# R7FA2E1A7_LED.net
KiCad netlist of a schematic drawn in EasyEDA Pro
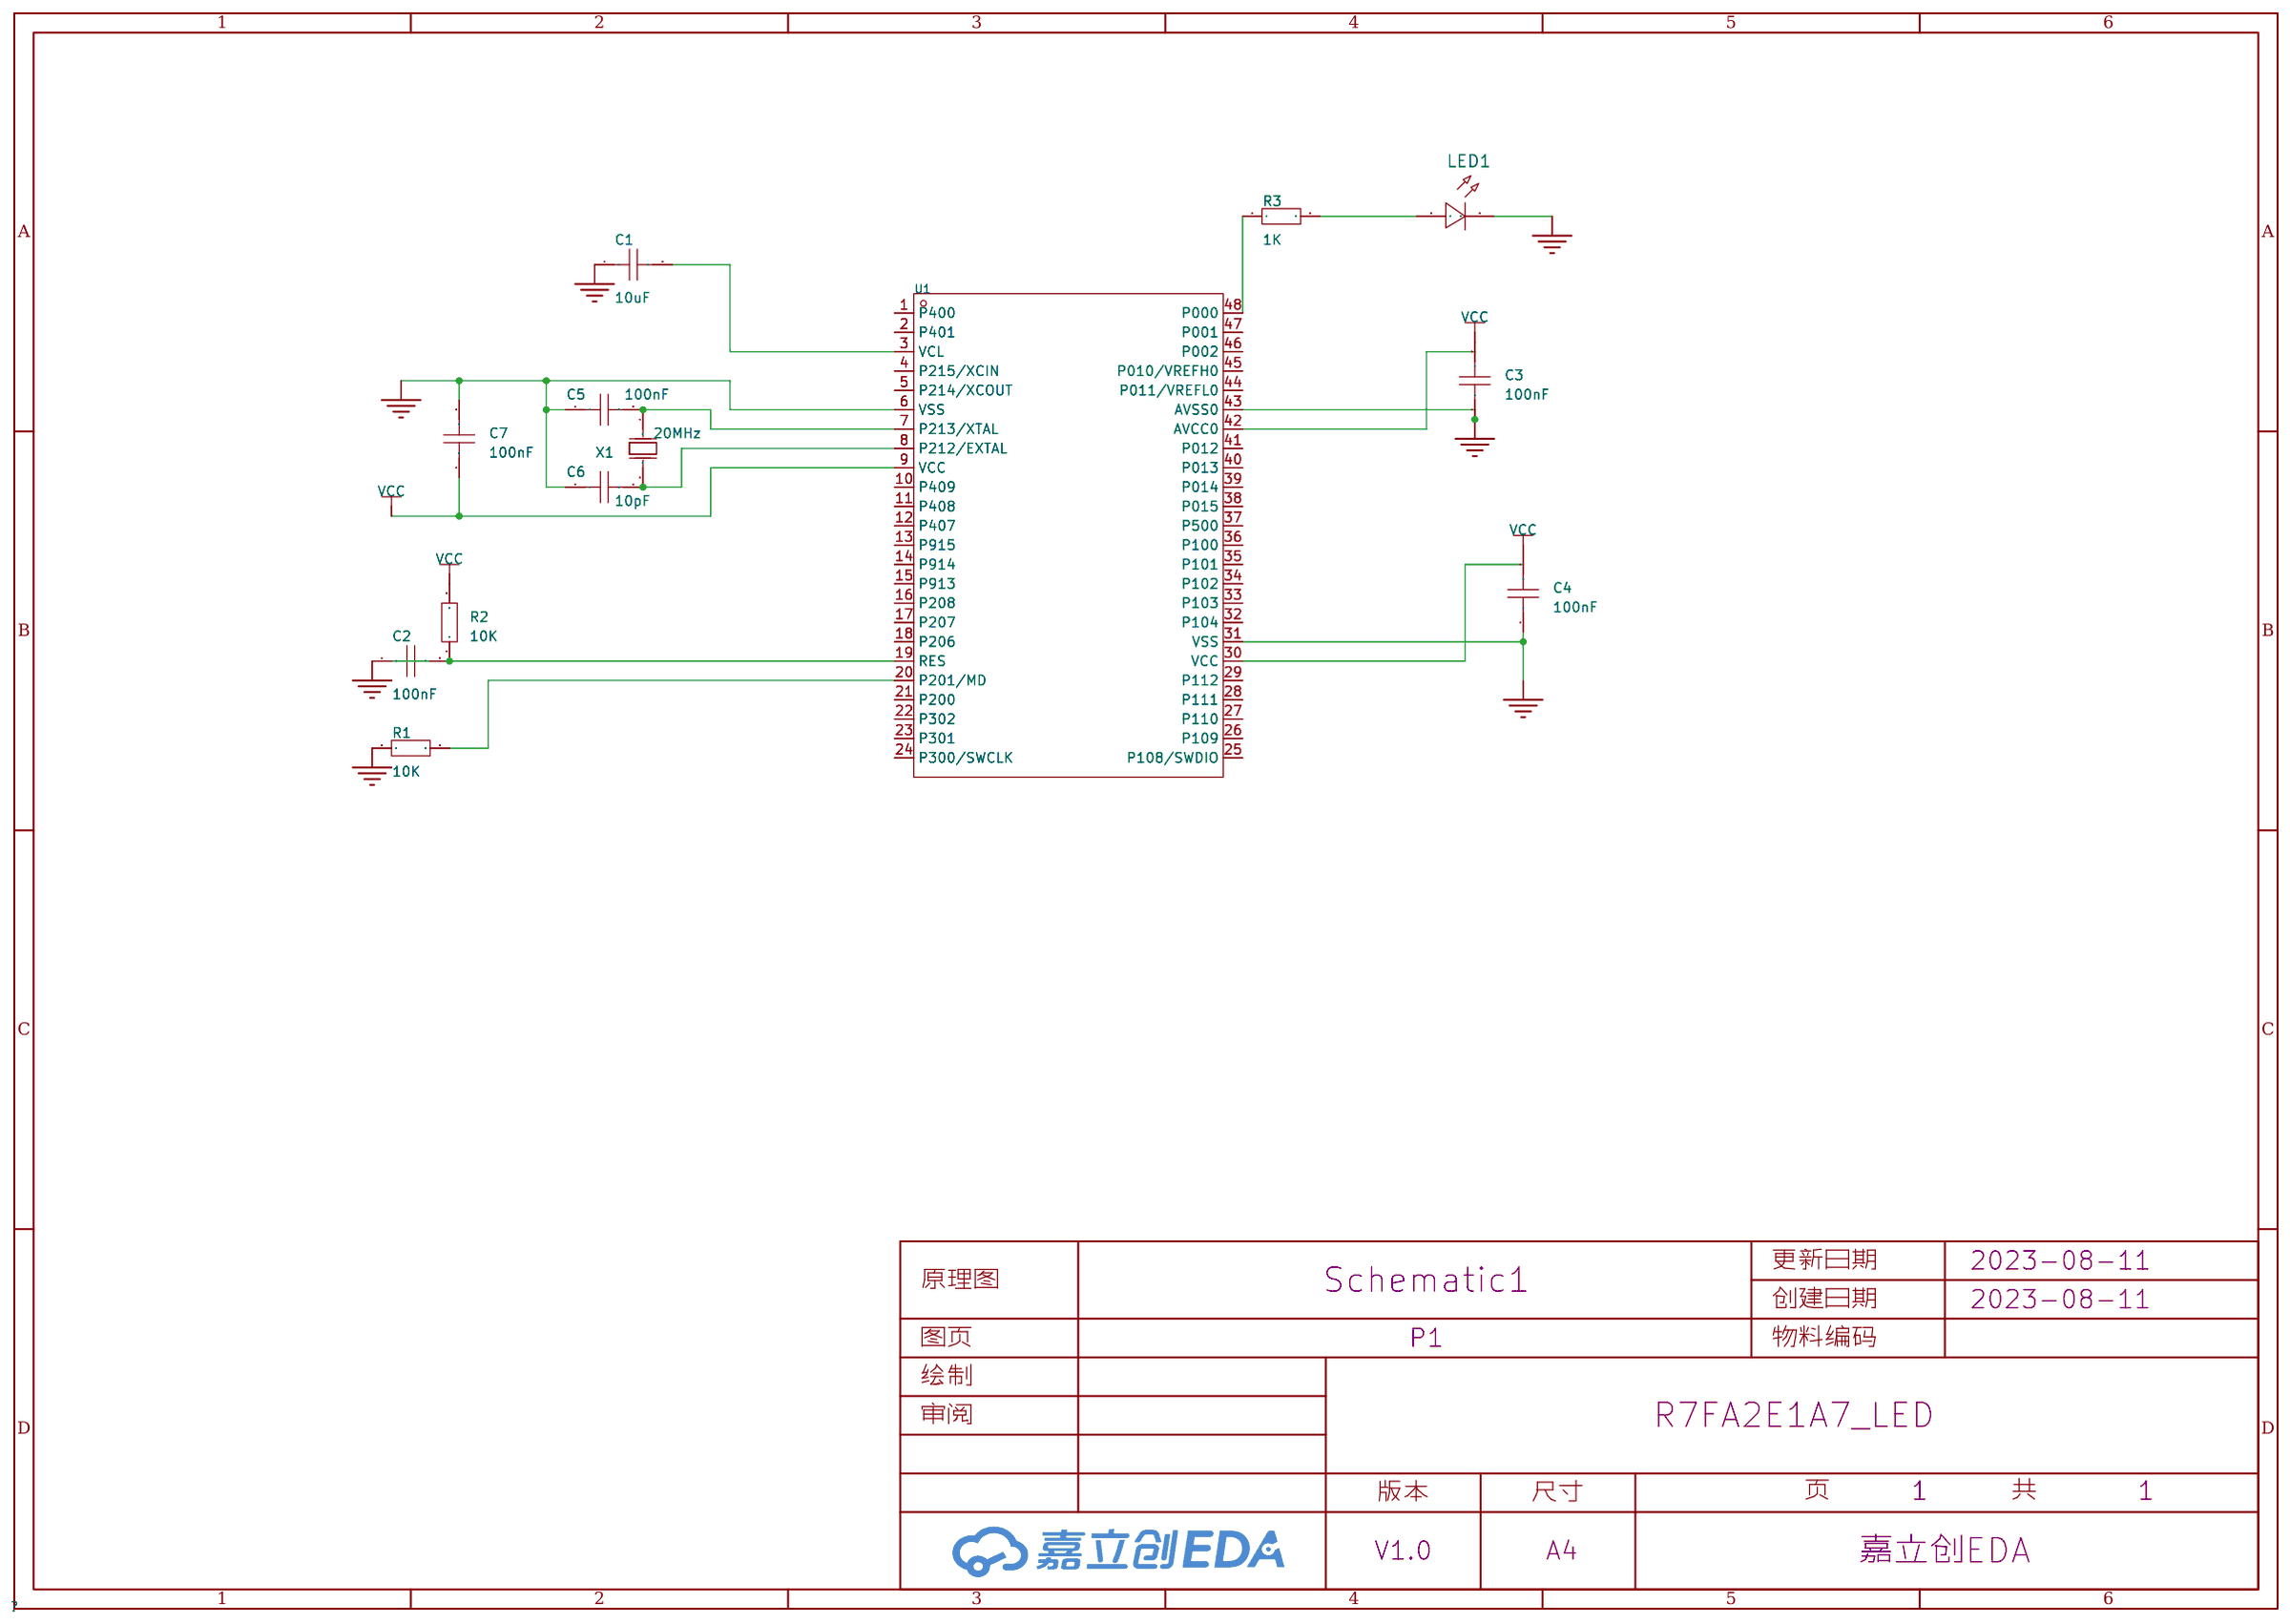
[diagram p0: schematic sheet]

(export (version "E")
  (design (tool "Eeschema 10.0.6"))
  (components
    (comp (ref "C1")
      (value "10uF")
      (footprint "easyedapro:C0603")
      (libsource (lib "easyedapro") (part "CapAcitance"))
    )
    (comp (ref "C2")
      (value "100nF")
      (footprint "easyedapro:C0603")
      (libsource (lib "easyedapro") (part "CapAcitance"))
    )
    (comp (ref "C3")
      (value "100nF")
      (footprint "easyedapro:C0603")
      (libsource (lib "easyedapro") (part "CapAcitance"))
    )
    (comp (ref "C4")
      (value "100nF")
      (footprint "easyedapro:C0603")
      (libsource (lib "easyedapro") (part "CapAcitance"))
    )
    (comp (ref "C5")
      (value "100nF")
      (footprint "easyedapro:C0603")
      (libsource (lib "easyedapro") (part "CapAcitance"))
    )
    (comp (ref "C6")
      (value "10pF")
      (footprint "easyedapro:C0603")
      (libsource (lib "easyedapro") (part "CapAcitance"))
    )
    (comp (ref "C7")
      (value "100nF")
      (footprint "easyedapro:C0603")
      (libsource (lib "easyedapro") (part "CapAcitance"))
    )
    (comp (ref "LED1")
      (value "~")
      (footprint "easyedapro:LED_0603")
      (libsource (lib "easyedapro") (part "LED_R"))
    )
    (comp (ref "R1") (value "10K") (footprint "easyedapro:R0603") (libsource (lib "easyedapro") (part "电阻")))
    (comp (ref "R2") (value "10K") (footprint "easyedapro:R0603") (libsource (lib "easyedapro") (part "电阻")))
    (comp (ref "R3") (value "1K") (footprint "easyedapro:R0603") (libsource (lib "easyedapro") (part "电阻")))
    (comp (ref "U1")
      (value "R7FA2E1A72DFL#AA0")
      (footprint "easyedapro:LQFP-48_L7.0-W7.0-P0.50-LS9.0-BL")
      (description "CPU内核:ARM Cortex-M23;CPU最大主频:48MHz;工作电压范围:1.6V~5.5V;程序存储容量:64KB;RAM总容量:16KB;GPIO端口数量:40;")
      (fields (field (name "Manufacturer") "RENESAS(瑞萨)/IDT"))
      (libsource (lib "easyedapro") (part "R7FA2E1A72DFL#AA0"))
    )
    (comp (ref "X1")
      (value "20MHz")
      (footprint "easyedapro:OSC-TH_L10.0-W4.5-P5.00")
      (description "频率:20MHz;频率公差:±10ppm;负载电容:15pF;")
      (fields (field (name "Manufacturer Part") "X49SD20MPB2SC") (field (name "Manufacturer") "YXC(扬兴晶振)"))
      (libsource (lib "easyedapro") (part "X49SD20MPB2SC"))
    )
  )
  (nets
    (net (code "1") (name "GND") (class "Default")
      (node (ref "C1") (pin "1") (pinfunction "1_1") (pintype "input"))
      (node (ref "C2") (pin "1") (pinfunction "1_1") (pintype "input"))
      (node (ref "C3") (pin "1") (pinfunction "1_1") (pintype "input"))
      (node (ref "C4") (pin "1") (pinfunction "1_1") (pintype "input"))
      (node (ref "C5") (pin "1") (pinfunction "1_1") (pintype "input"))
      (node (ref "C6") (pin "1") (pinfunction "1_1") (pintype "input"))
      (node (ref "C7") (pin "2") (pinfunction "2_2") (pintype "input"))
      (node (ref "LED1") (pin "1") (pinfunction "C_1") (pintype "input"))
      (node (ref "R1") (pin "1") (pinfunction "1_1") (pintype "input"))
      (node (ref "U1") (pin "31") (pinfunction "VSS_31") (pintype "input"))
      (node (ref "U1") (pin "43") (pinfunction "AVSS0_43") (pintype "input"))
      (node (ref "U1") (pin "6") (pinfunction "VSS_6") (pintype "input"))
    )
    (net (code "2") (name "Net-(LED1-A)") (class "Default")
      (node (ref "LED1") (pin "2") (pinfunction "A_2") (pintype "input"))
      (node (ref "R3") (pin "2") (pinfunction "2_2") (pintype "input"))
    )
    (net (code "3") (name "Net-(U1-P000)") (class "Default")
      (node (ref "R3") (pin "1") (pinfunction "1_1") (pintype "input"))
      (node (ref "U1") (pin "48") (pinfunction "P000_48") (pintype "input"))
    )
    (net (code "4") (name "Net-(U1-P201{slash}MD)") (class "Default")
      (node (ref "R1") (pin "2") (pinfunction "2_2") (pintype "input"))
      (node (ref "U1") (pin "20") (pinfunction "P201/MD_20") (pintype "input"))
    )
    (net (code "5") (name "Net-(U1-P212{slash}EXTAL)") (class "Default")
      (node (ref "C6") (pin "2") (pinfunction "2_2") (pintype "input"))
      (node (ref "U1") (pin "8") (pinfunction "P212/EXTAL_8") (pintype "input"))
      (node (ref "X1") (pin "2") (pinfunction "OSC2_2") (pintype "input"))
    )
    (net (code "6") (name "Net-(U1-P213{slash}XTAL)") (class "Default")
      (node (ref "C5") (pin "2") (pinfunction "2_2") (pintype "input"))
      (node (ref "U1") (pin "7") (pinfunction "P213/XTAL_7") (pintype "input"))
      (node (ref "X1") (pin "1") (pinfunction "OSC1_1") (pintype "input"))
    )
    (net (code "7") (name "Net-(U1-RES)") (class "Default")
      (node (ref "C2") (pin "2") (pinfunction "2_2") (pintype "input"))
      (node (ref "R2") (pin "1") (pinfunction "1_1") (pintype "input"))
      (node (ref "U1") (pin "19") (pinfunction "RES_19") (pintype "input"))
    )
    (net (code "8") (name "Net-(U1-VCL)") (class "Default")
      (node (ref "C1") (pin "2") (pinfunction "2_2") (pintype "input"))
      (node (ref "U1") (pin "3") (pinfunction "VCL_3") (pintype "input"))
    )
    (net (code "9") (name "VCC") (class "Default")
      (node (ref "C3") (pin "2") (pinfunction "2_2") (pintype "input"))
      (node (ref "C4") (pin "2") (pinfunction "2_2") (pintype "input"))
      (node (ref "C7") (pin "1") (pinfunction "1_1") (pintype "input"))
      (node (ref "R2") (pin "2") (pinfunction "2_2") (pintype "input"))
      (node (ref "U1") (pin "9") (pinfunction "VCC_9") (pintype "input"))
    )
    (net (code "10") (name "unconnected-(U1-AVCC0-Pad42)") (class "Default")
      (node (ref "U1") (pin "42") (pinfunction "AVCC0_42") (pintype "input"))
    )
    (net (code "11") (name "unconnected-(U1-P001-Pad47)") (class "Default")
      (node (ref "U1") (pin "47") (pinfunction "P001_47") (pintype "input"))
    )
    (net (code "12") (name "unconnected-(U1-P002-Pad46)") (class "Default")
      (node (ref "U1") (pin "46") (pinfunction "P002_46") (pintype "input"))
    )
    (net (code "13") (name "unconnected-(U1-P010{slash}VREFH0-Pad45)") (class "Default")
      (node (ref "U1") (pin "45") (pinfunction "P010/VREFH0_45") (pintype "input"))
    )
    (net (code "14") (name "unconnected-(U1-P011{slash}VREFL0-Pad44)") (class "Default")
      (node (ref "U1") (pin "44") (pinfunction "P011/VREFL0_44") (pintype "input"))
    )
    (net (code "15") (name "unconnected-(U1-P012-Pad41)") (class "Default")
      (node (ref "U1") (pin "41") (pinfunction "P012_41") (pintype "input"))
    )
    (net (code "16") (name "unconnected-(U1-P013-Pad40)") (class "Default")
      (node (ref "U1") (pin "40") (pinfunction "P013_40") (pintype "input"))
    )
    (net (code "17") (name "unconnected-(U1-P014-Pad39)") (class "Default")
      (node (ref "U1") (pin "39") (pinfunction "P014_39") (pintype "input"))
    )
    (net (code "18") (name "unconnected-(U1-P015-Pad38)") (class "Default")
      (node (ref "U1") (pin "38") (pinfunction "P015_38") (pintype "input"))
    )
    (net (code "19") (name "unconnected-(U1-P100-Pad36)") (class "Default")
      (node (ref "U1") (pin "36") (pinfunction "P100_36") (pintype "input"))
    )
    (net (code "20") (name "unconnected-(U1-P101-Pad35)") (class "Default")
      (node (ref "U1") (pin "35") (pinfunction "P101_35") (pintype "input"))
    )
    (net (code "21") (name "unconnected-(U1-P102-Pad34)") (class "Default")
      (node (ref "U1") (pin "34") (pinfunction "P102_34") (pintype "input"))
    )
    (net (code "22") (name "unconnected-(U1-P103-Pad33)") (class "Default")
      (node (ref "U1") (pin "33") (pinfunction "P103_33") (pintype "input"))
    )
    (net (code "23") (name "unconnected-(U1-P104-Pad32)") (class "Default")
      (node (ref "U1") (pin "32") (pinfunction "P104_32") (pintype "input"))
    )
    (net (code "24") (name "unconnected-(U1-P108{slash}SWDIO-Pad25)") (class "Default")
      (node (ref "U1") (pin "25") (pinfunction "P108/SWDIO_25") (pintype "input"))
    )
    (net (code "25") (name "unconnected-(U1-P109-Pad26)") (class "Default")
      (node (ref "U1") (pin "26") (pinfunction "P109_26") (pintype "input"))
    )
    (net (code "26") (name "unconnected-(U1-P110-Pad27)") (class "Default")
      (node (ref "U1") (pin "27") (pinfunction "P110_27") (pintype "input"))
    )
    (net (code "27") (name "unconnected-(U1-P111-Pad28)") (class "Default")
      (node (ref "U1") (pin "28") (pinfunction "P111_28") (pintype "input"))
    )
    (net (code "28") (name "unconnected-(U1-P112-Pad29)") (class "Default")
      (node (ref "U1") (pin "29") (pinfunction "P112_29") (pintype "input"))
    )
    (net (code "29") (name "unconnected-(U1-P200-Pad21)") (class "Default")
      (node (ref "U1") (pin "21") (pinfunction "P200_21") (pintype "input"))
    )
    (net (code "30") (name "unconnected-(U1-P206-Pad18)") (class "Default")
      (node (ref "U1") (pin "18") (pinfunction "P206_18") (pintype "input"))
    )
    (net (code "31") (name "unconnected-(U1-P207-Pad17)") (class "Default")
      (node (ref "U1") (pin "17") (pinfunction "P207_17") (pintype "input"))
    )
    (net (code "32") (name "unconnected-(U1-P208-Pad16)") (class "Default")
      (node (ref "U1") (pin "16") (pinfunction "P208_16") (pintype "input"))
    )
    (net (code "33") (name "unconnected-(U1-P214{slash}XCOUT-Pad5)") (class "Default")
      (node (ref "U1") (pin "5") (pinfunction "P214/XCOUT_5") (pintype "input"))
    )
    (net (code "34") (name "unconnected-(U1-P215{slash}XCIN-Pad4)") (class "Default")
      (node (ref "U1") (pin "4") (pinfunction "P215/XCIN_4") (pintype "input"))
    )
    (net (code "35") (name "unconnected-(U1-P300{slash}SWCLK-Pad24)") (class "Default")
      (node (ref "U1") (pin "24") (pinfunction "P300/SWCLK_24") (pintype "input"))
    )
    (net (code "36") (name "unconnected-(U1-P301-Pad23)") (class "Default")
      (node (ref "U1") (pin "23") (pinfunction "P301_23") (pintype "input"))
    )
    (net (code "37") (name "unconnected-(U1-P302-Pad22)") (class "Default")
      (node (ref "U1") (pin "22") (pinfunction "P302_22") (pintype "input"))
    )
    (net (code "38") (name "unconnected-(U1-P400-Pad1)") (class "Default")
      (node (ref "U1") (pin "1") (pinfunction "P400_1") (pintype "input"))
    )
    (net (code "39") (name "unconnected-(U1-P401-Pad2)") (class "Default")
      (node (ref "U1") (pin "2") (pinfunction "P401_2") (pintype "input"))
    )
    (net (code "40") (name "unconnected-(U1-P407-Pad12)") (class "Default")
      (node (ref "U1") (pin "12") (pinfunction "P407_12") (pintype "input"))
    )
    (net (code "41") (name "unconnected-(U1-P408-Pad11)") (class "Default")
      (node (ref "U1") (pin "11") (pinfunction "P408_11") (pintype "input"))
    )
    (net (code "42") (name "unconnected-(U1-P409-Pad10)") (class "Default")
      (node (ref "U1") (pin "10") (pinfunction "P409_10") (pintype "input"))
    )
    (net (code "43") (name "unconnected-(U1-P500-Pad37)") (class "Default")
      (node (ref "U1") (pin "37") (pinfunction "P500_37") (pintype "input"))
    )
    (net (code "44") (name "unconnected-(U1-P913-Pad15)") (class "Default")
      (node (ref "U1") (pin "15") (pinfunction "P913_15") (pintype "input"))
    )
    (net (code "45") (name "unconnected-(U1-P914-Pad14)") (class "Default")
      (node (ref "U1") (pin "14") (pinfunction "P914_14") (pintype "input"))
    )
    (net (code "46") (name "unconnected-(U1-P915-Pad13)") (class "Default")
      (node (ref "U1") (pin "13") (pinfunction "P915_13") (pintype "input"))
    )
    (net (code "47") (name "unconnected-(U1-VCC-Pad30)") (class "Default")
      (node (ref "U1") (pin "30") (pinfunction "VCC_30") (pintype "input"))
    )
  )
)
